# power.net
KiCad netlist of a schematic drawn in Altium Designer
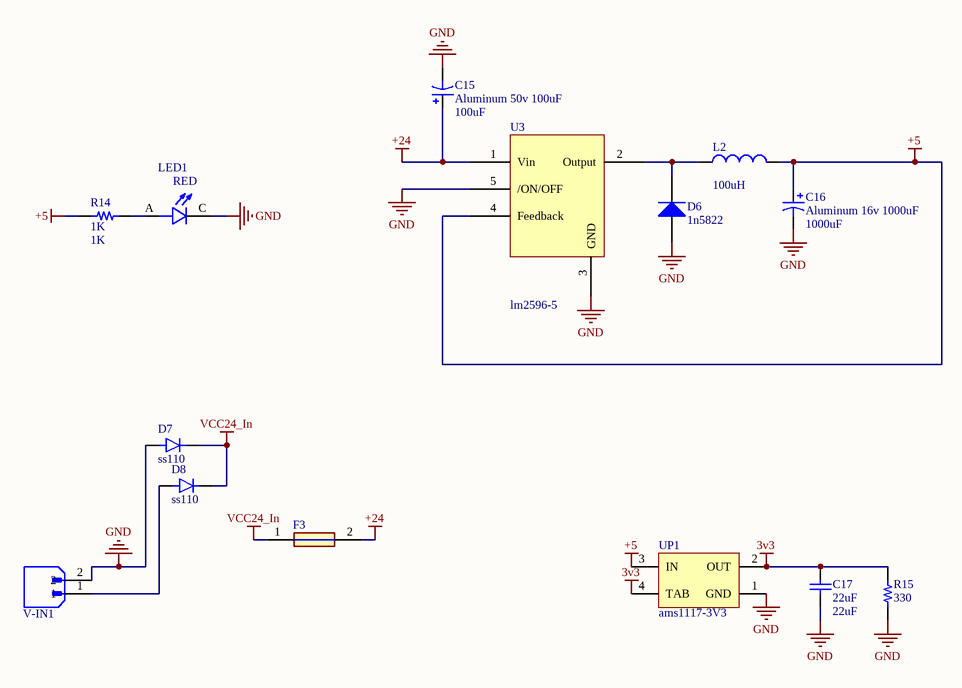
[diagram p0: power.SchDoc]

(export (version "E")
  (design (tool "Eeschema 10.0.6"))
  (components
    (comp (ref "C15")
      (value "Aluminum 50v 100uF")
      (footprint "Cap SMD 100UF 35~50v")
      (description "CAP POLAR SMD")
      (fields (field (name "ALTIUM_VALUE") "100uF") (field (name "PUBLISHER") "Altium Limited"))
      (libsource (lib "Miscellaneous Devices") (part "Cap Pol1"))
    )
    (comp (ref "C16")
      (value "Aluminum 16v 1000uF")
      (footprint "CAP SMD 1000UF 16V")
      (description "CAP POLAR SMD")
      (fields (field (name "ALTIUM_VALUE") "1000uF") (field (name "PUBLISHER") "Altium Limited"))
      (libsource (lib "Miscellaneous Devices") (part "Cap Pol1"))
    )
    (comp (ref "C17")
      (value "22uF")
      (footprint "0603C")
      (description "CAP SMD 0603")
      (fields (field (name "ALTIUM_VALUE") "22uF") (field (name "PUBLISHER") "Altium Limited"))
      (libsource (lib "Miscellaneous Devices") (part "Cap"))
    )
    (comp (ref "D6")
      (value "1n5822")
      (footprint "SMA DIODE 2")
      (description "1 Amp schottky Diode SMA")
      (fields (field (name "PUBLISHER") "Altium Limited"))
      (libsource (lib "Miscellaneous Devices") (part "Diode 1N4007"))
    )
    (comp (ref "D7")
      (value "ss110")
      (footprint "ss110")
      (description "Diode Super Barrier 60V 500mA Surface Mount SOD-123")
      (fields (field (name "MP") "SBR0560S1-7") (field (name "MF") "Diodes Inc."))
      (libsource (lib "diode") (part "SBR0560S1-7"))
    )
    (comp (ref "D8")
      (value "ss110")
      (footprint "ss110")
      (description "Diode Super Barrier 60V 500mA Surface Mount SOD-123")
      (fields (field (name "MP") "SBR0560S1-7") (field (name "MF") "Diodes Inc."))
      (libsource (lib "diode") (part "SBR0560S1-7"))
    )
    (comp (ref "F3")
      (value "fuse 2amp")
      (footprint "1206 FUSE")
      (description "Fuse 1206")
      (fields (field (name "MANUFACTURER_PART_NUMBER") "1206SFS200F/63-2"))
      (libsource (lib "robot1") (part "1206SFS200F_63-2"))
    )
    (comp (ref "L2")
      (value "100uH")
      (footprint "inductor")
      (description "Inductor 12*12mm")
      (fields (field (name "Comment") "inductor 100uH") (field (name "PUBLISHER") "Altium Limited"))
      (libsource (lib "Miscellaneous Devices") (part "Inductor"))
    )
    (comp (ref "LED1")
      (value "LED RED")
      (footprint "LED_7012X1")
      (description "LED SMD 0805 RED")
      (fields (field (name "MP") "7012X1"))
      (libsource (lib "LED0805") (part "7012X1"))
    )
    (comp (ref "R14")
      (value "1K")
      (footprint "0603R")
      (description "RES SMD 0603")
      (fields (field (name "PART NUMBER") "RCS0805100KFKEA") (field (name "ALTIUM_VALUE") "1K"))
      (libsource (lib "lamp control-ver2") (part "Resistor"))
    )
    (comp (ref "R15")
      (value "330")
      (footprint "0603R")
      (description "RES SMD 0603")
      (fields (field (name "PART NUMBER") "RCS0805100KFKEA"))
      (libsource (lib "lamp control-ver2") (part "Resistor"))
    )
    (comp (ref "U3") (value "lm2596-5") (footprint "2596") (libsource (lib "No.2") (part "lm2596")))
    (comp (ref "UP1")
      (value "ams1117-3V3")
      (footprint "SOT223")
      (description "3.3 Volt, 800mA SOT-223")
      (fields (field (name "DESIGNER") "Ali Hafizi"))
      (libsource (lib "monitor_panel") (part "AMS1117-x.x"))
    )
    (comp (ref "V-IN1")
      (value "Phoenix")
      (footprint "AMPHENOL_OQ0271510000G")
      (description "Phoenix Terminal Right 2PIN")
      (fields (field (name "MP") "OQ0271510000G") (field (name "MF") "Amphenol Anytek"))
      (libsource (lib "phoenix2") (part "OQ0271510000G"))
    )
  )
  (nets
    (net (code "1") (name "+5") (class "Default")
      (node (ref "C16") (pin "1") (pinfunction "1_1") (pintype "passive"))
      (node (ref "L2") (pin "2") (pinfunction "2_2") (pintype "passive"))
      (node (ref "R14") (pin "1") (pinfunction "1_1") (pintype "passive"))
      (node (ref "U3") (pin "4") (pinfunction "Feedback_4") (pintype "power_in"))
      (node (ref "UP1") (pin "3") (pinfunction "IN_3") (pintype "power_in"))
    )
    (net (code "2") (name "+24") (class "Default")
      (node (ref "C15") (pin "1") (pinfunction "1_1") (pintype "passive"))
      (node (ref "F3") (pin "2") (pinfunction "2_2") (pintype "passive"))
      (node (ref "U3") (pin "1") (pinfunction "Vin_1") (pintype "power_in"))
    )
    (net (code "3") (name "3v3") (class "Default")
      (node (ref "C17") (pin "2") (pinfunction "2_2") (pintype "passive"))
      (node (ref "R15") (pin "1") (pinfunction "1_1") (pintype "passive"))
      (node (ref "UP1") (pin "2") (pinfunction "OUT_2") (pintype "power_in"))
      (node (ref "UP1") (pin "4") (pinfunction "TAB_4") (pintype "power_in"))
    )
    (net (code "4") (name "GND") (class "Default")
      (node (ref "C15") (pin "2") (pinfunction "2_2") (pintype "passive"))
      (node (ref "C16") (pin "2") (pinfunction "2_2") (pintype "passive"))
      (node (ref "C17") (pin "1") (pinfunction "1_1") (pintype "passive"))
      (node (ref "D6") (pin "1") (pinfunction "A_1") (pintype "passive"))
      (node (ref "D7") (pin "A") (pinfunction "A_A") (pintype "passive"))
      (node (ref "LED1") (pin "C") (pinfunction "C_C") (pintype "passive"))
      (node (ref "R15") (pin "2") (pinfunction "2_2") (pintype "passive"))
      (node (ref "U3") (pin "3") (pinfunction "GND_3") (pintype "power_in"))
      (node (ref "U3") (pin "5") (pinfunction "/ON/OFF_5") (pintype "power_in"))
      (node (ref "UP1") (pin "1") (pinfunction "GND_1") (pintype "power_in"))
      (node (ref "V-IN1") (pin "2") (pinfunction "2_2") (pintype "passive"))
    )
    (net (code "5") (name "Net-(D6-K)") (class "Default")
      (node (ref "D6") (pin "2") (pinfunction "K_2") (pintype "passive"))
      (node (ref "L2") (pin "1") (pinfunction "1_1") (pintype "passive"))
      (node (ref "U3") (pin "2") (pinfunction "Output_2") (pintype "power_in"))
    )
    (net (code "6") (name "Net-(D8-PadA)") (class "Default")
      (node (ref "D8") (pin "A") (pinfunction "A_A") (pintype "passive"))
      (node (ref "V-IN1") (pin "1") (pinfunction "1_1") (pintype "passive"))
    )
    (net (code "7") (name "Net-(LED1-PadA)") (class "Default")
      (node (ref "LED1") (pin "A") (pinfunction "A_A") (pintype "passive"))
      (node (ref "R14") (pin "2") (pinfunction "2_2") (pintype "passive"))
    )
    (net (code "8") (name "VCC24_In") (class "Default")
      (node (ref "D7") (pin "C") (pinfunction "K_C") (pintype "passive"))
      (node (ref "D8") (pin "C") (pinfunction "K_C") (pintype "passive"))
      (node (ref "F3") (pin "1") (pinfunction "1_1") (pintype "passive"))
    )
  )
)
